# 5v_dcreg.net
KiCad netlist of a schematic drawn in EAGLE
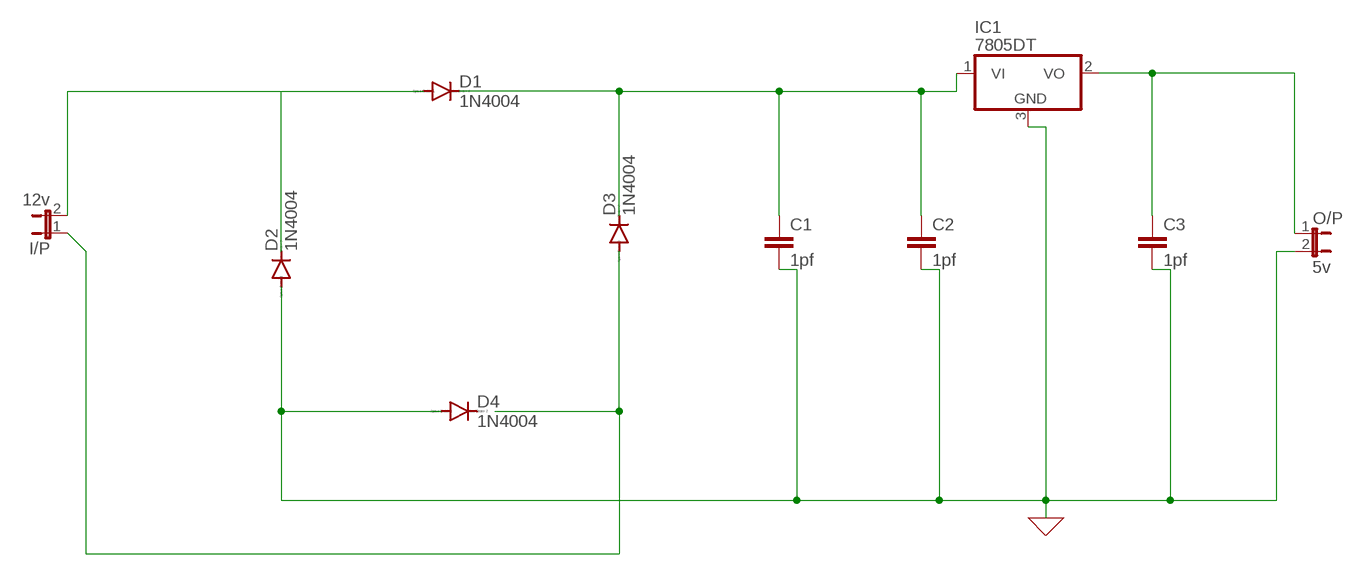
[diagram p0: schematic, sheet 1]

(export (version "E")
  (design (tool "Eeschema 10.0.6"))
  (components
    (comp (ref "C1")
      (value "1pf")
      (footprint "eagle-import:C2.5-3")
      (libsource (lib "eagle-import") (part "C2,5-3"))
    )
    (comp (ref "C2")
      (value "1pf")
      (footprint "eagle-import:C2.5-3")
      (libsource (lib "eagle-import") (part "C2,5-3"))
    )
    (comp (ref "C3")
      (value "1pf")
      (footprint "eagle-import:C2.5-3")
      (libsource (lib "eagle-import") (part "C2,5-3"))
    )
    (comp (ref "D1")
      (value "1N4004")
      (footprint "eagle-import:DO41-10")
      (libsource (lib "eagle-import") (part "1N4004"))
    )
    (comp (ref "D2")
      (value "1N4004")
      (footprint "eagle-import:DO41-10")
      (libsource (lib "eagle-import") (part "1N4004"))
    )
    (comp (ref "D3")
      (value "1N4004")
      (footprint "eagle-import:DO41-10")
      (libsource (lib "eagle-import") (part "1N4004"))
    )
    (comp (ref "D4")
      (value "1N4004")
      (footprint "eagle-import:DO41-10")
      (libsource (lib "eagle-import") (part "1N4004"))
    )
    (comp (ref "I/P")
      (value "12v")
      (footprint "eagle-import:JP1")
      (libsource (lib "eagle-import") (part "JP1E"))
    )
    (comp (ref "IC1")
      (value "7805DT")
      (footprint "eagle-import:TO252")
      (libsource (lib "eagle-import") (part "78DT05"))
    )
    (comp (ref "O/P")
      (value "5v")
      (footprint "eagle-import:JP1")
      (libsource (lib "eagle-import") (part "JP1E"))
    )
  )
  (nets
    (net (code "1") (name "GND") (class "Default")
      (node (ref "C1") (pin "2") (pinfunction "2_2") (pintype "passive"))
      (node (ref "C2") (pin "2") (pinfunction "2_2") (pintype "passive"))
      (node (ref "C3") (pin "2") (pinfunction "2_2") (pintype "passive"))
      (node (ref "D2") (pin "A") (pinfunction "A_A") (pintype "passive"))
      (node (ref "D4") (pin "A") (pinfunction "A_A") (pintype "passive"))
      (node (ref "IC1") (pin "3") (pinfunction "GND_3") (pintype "passive"))
      (node (ref "O/P") (pin "2") (pinfunction "2_2") (pintype "passive"))
    )
    (net (code "2") (name "Net-(D1-PadA)") (class "Default")
      (node (ref "D1") (pin "A") (pinfunction "A_A") (pintype "passive"))
      (node (ref "D2") (pin "C") (pinfunction "C_C") (pintype "passive"))
      (node (ref "I/P") (pin "2") (pinfunction "2_2") (pintype "passive"))
    )
    (net (code "3") (name "Net-(D3-PadA)") (class "Default")
      (node (ref "D3") (pin "A") (pinfunction "A_A") (pintype "passive"))
      (node (ref "I/P") (pin "1") (pinfunction "1_1") (pintype "passive"))
    )
    (net (code "4") (name "Net-(IC1-VI)") (class "Default")
      (node (ref "C1") (pin "1") (pinfunction "1_1") (pintype "passive"))
      (node (ref "C2") (pin "1") (pinfunction "1_1") (pintype "passive"))
      (node (ref "D1") (pin "C") (pinfunction "C_C") (pintype "passive"))
      (node (ref "D3") (pin "C") (pinfunction "C_C") (pintype "passive"))
      (node (ref "IC1") (pin "1") (pinfunction "VI_1") (pintype "input"))
    )
    (net (code "5") (name "Net-(IC1-VO)") (class "Default")
      (node (ref "C3") (pin "1") (pinfunction "1_1") (pintype "passive"))
      (node (ref "IC1") (pin "2") (pinfunction "VO_2") (pintype "passive"))
      (node (ref "O/P") (pin "1") (pinfunction "1_1") (pintype "passive"))
    )
    (net (code "6") (name "unconnected-(D4-PadC)") (class "Default")
      (node (ref "D4") (pin "C") (pinfunction "C_C") (pintype "passive"))
    )
  )
)
